# hmc241.net
KiCad netlist of a schematic drawn in EasyEDA Pro
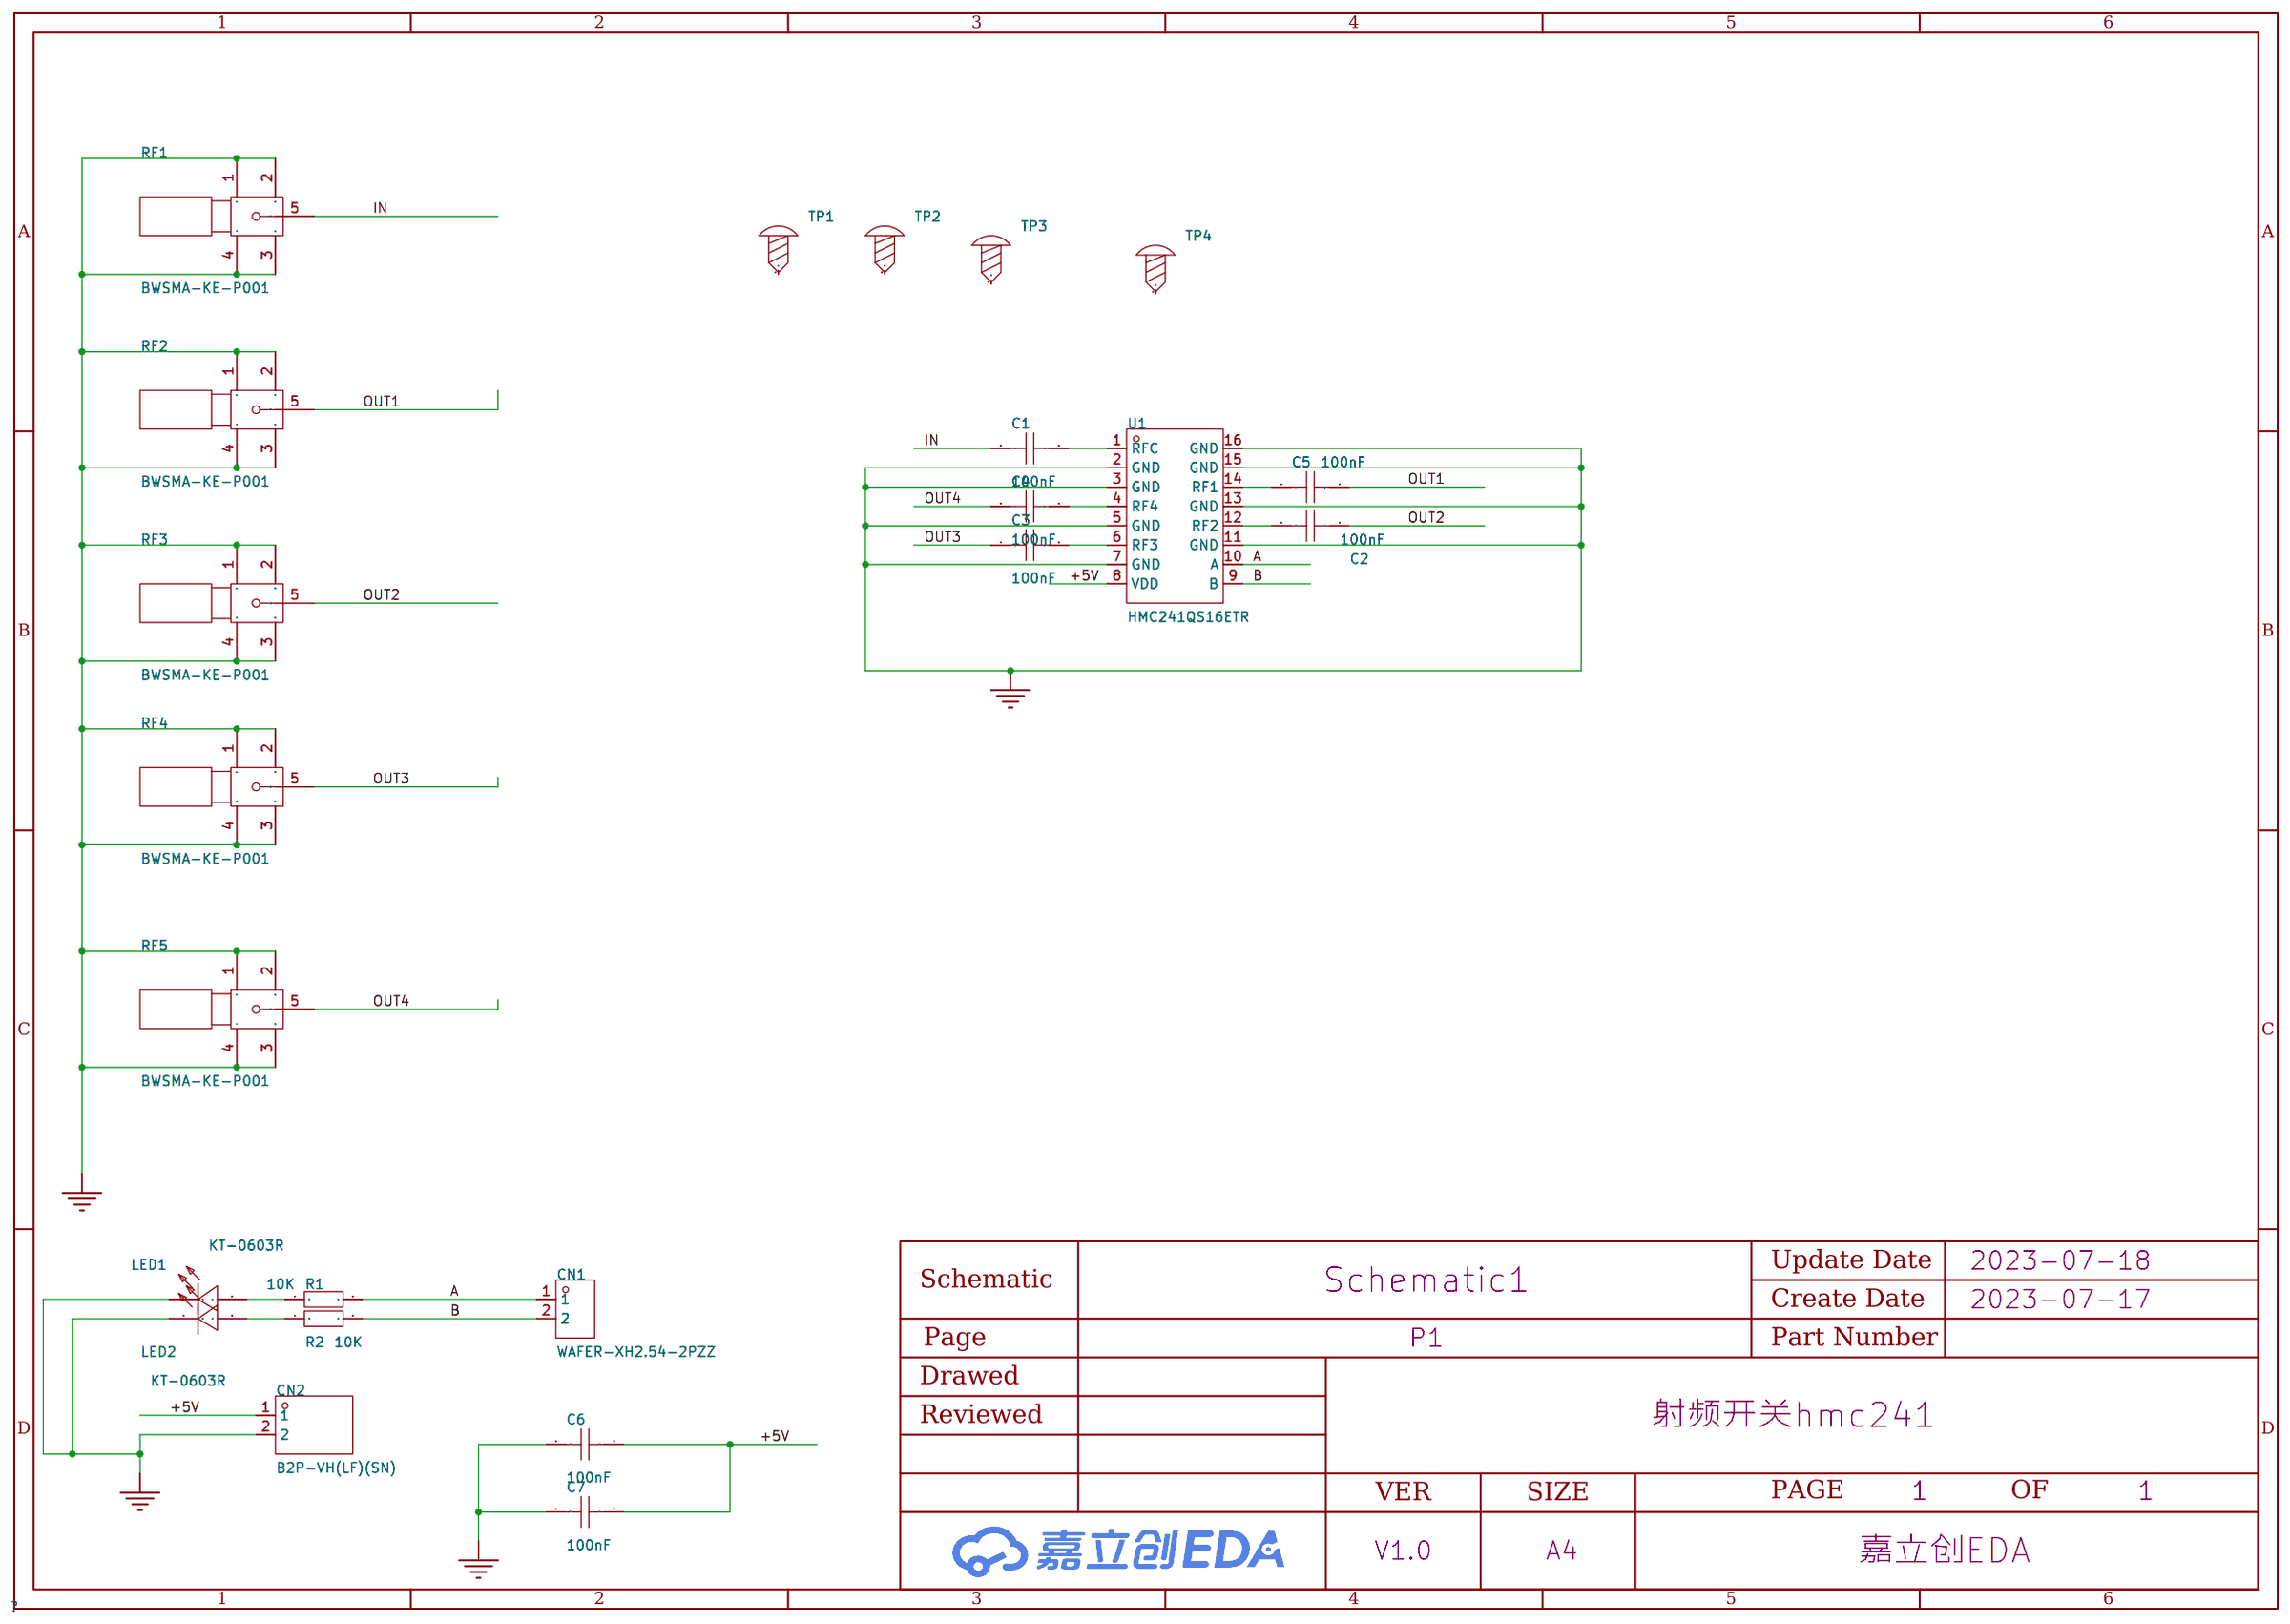
[diagram p0: schematic sheet]

(export (version "E")
  (design (tool "Eeschema 10.0.6"))
  (components
    (comp (ref "C1")
      (value "100nF")
      (footprint "easyedapro:C0603")
      (libsource (lib "easyedapro") (part "CapAcitance"))
    )
    (comp (ref "C2")
      (value "100nF")
      (footprint "easyedapro:C0603")
      (libsource (lib "easyedapro") (part "CapAcitance"))
    )
    (comp (ref "C3")
      (value "100nF")
      (footprint "easyedapro:C0603")
      (libsource (lib "easyedapro") (part "CapAcitance"))
    )
    (comp (ref "C4")
      (value "100nF")
      (footprint "easyedapro:C0603")
      (libsource (lib "easyedapro") (part "CapAcitance"))
    )
    (comp (ref "C5")
      (value "100nF")
      (footprint "easyedapro:C0603")
      (libsource (lib "easyedapro") (part "CapAcitance"))
    )
    (comp (ref "C6")
      (value "100nF")
      (footprint "easyedapro:C0603")
      (libsource (lib "easyedapro") (part "CapAcitance"))
    )
    (comp (ref "C7")
      (value "100nF")
      (footprint "easyedapro:C0603")
      (libsource (lib "easyedapro") (part "CapAcitance"))
    )
    (comp (ref "CN1")
      (value "WAFER-XH2.54-2PZZ")
      (footprint "easyedapro:CONN-TH_XH2.54-2P")
      (fields (field (name "Manufacturer") "XUNPU(讯普)"))
      (libsource (lib "easyedapro") (part "WAFER-XH2.54-2PZZ"))
    )
    (comp (ref "CN2")
      (value "B2P-VH(LF)(SN)")
      (footprint "easyedapro:CONN-TH_B2P-VH-LF-SN")
      (description "参考系列:VH;间距:3.96mm;插针结构:1x2P;排数:1;每排PIN数:2;行距:-;安装方式:-;触头材质:黄铜;")
      (fields (field (name "Manufacturer") "JST"))
      (libsource (lib "easyedapro") (part "B2P-VH (LF)(SN)"))
    )
    (comp (ref "LED1")
      (value "KT-0603R")
      (footprint "easyedapro:LED0603-RD")
      (description "发光颜色:红灯;二极管配置:-;透镜颜色:-;主波长:-;色温:-;功率:-;发光角度:-;安装方式:-;工作温度:-40°C~+85°C;")
      (fields (field (name "Manufacturer") "KENTO"))
      (libsource (lib "easyedapro") (part "KT-0603R"))
    )
    (comp (ref "LED2")
      (value "KT-0603R")
      (footprint "easyedapro:LED0603-RD")
      (description "发光颜色:红灯;二极管配置:-;透镜颜色:-;主波长:-;色温:-;功率:-;发光角度:-;安装方式:-;工作温度:-40°C~+85°C;")
      (fields (field (name "Manufacturer") "KENTO"))
      (libsource (lib "easyedapro") (part "KT-0603R"))
    )
    (comp (ref "R1") (value "10K") (footprint "easyedapro:R0603") (libsource (lib "easyedapro") (part "电阻")))
    (comp (ref "R2") (value "10K") (footprint "easyedapro:R0603") (libsource (lib "easyedapro") (part "电阻")))
    (comp (ref "RF1")
      (value "BWSMA-KE-P001")
      (footprint "easyedapro:SMA-SMD_BWSMA-KE-P001")
      (description "连接器类型:板端;射频系列:SMA;接口类型:内孔;端口数量:1;阻抗:50Ω;频率-最大值:12.4GHz;样式:偏脚;接口直径:5.2mm;接口长度/高度:-;工作温度范围:-;")
      (fields (field (name "Manufacturer") "BAT WIRELESS(蝙蝠无线)"))
      (libsource (lib "easyedapro") (part "BWSMA-KE-P001"))
    )
    (comp (ref "RF2")
      (value "BWSMA-KE-P001")
      (footprint "easyedapro:SMA-SMD_BWSMA-KE-P001")
      (description "连接器类型:板端;射频系列:SMA;接口类型:内孔;端口数量:1;阻抗:50Ω;频率-最大值:12.4GHz;样式:偏脚;接口直径:5.2mm;接口长度/高度:-;工作温度范围:-;")
      (fields (field (name "Manufacturer") "BAT WIRELESS(蝙蝠无线)"))
      (libsource (lib "easyedapro") (part "BWSMA-KE-P001"))
    )
    (comp (ref "RF3")
      (value "BWSMA-KE-P001")
      (footprint "easyedapro:SMA-SMD_BWSMA-KE-P001")
      (description "连接器类型:板端;射频系列:SMA;接口类型:内孔;端口数量:1;阻抗:50Ω;频率-最大值:12.4GHz;样式:偏脚;接口直径:5.2mm;接口长度/高度:-;工作温度范围:-;")
      (fields (field (name "Manufacturer") "BAT WIRELESS(蝙蝠无线)"))
      (libsource (lib "easyedapro") (part "BWSMA-KE-P001"))
    )
    (comp (ref "RF4")
      (value "BWSMA-KE-P001")
      (footprint "easyedapro:SMA-SMD_BWSMA-KE-P001")
      (description "连接器类型:板端;射频系列:SMA;接口类型:内孔;端口数量:1;阻抗:50Ω;频率-最大值:12.4GHz;样式:偏脚;接口直径:5.2mm;接口长度/高度:-;工作温度范围:-;")
      (fields (field (name "Manufacturer") "BAT WIRELESS(蝙蝠无线)"))
      (libsource (lib "easyedapro") (part "BWSMA-KE-P001"))
    )
    (comp (ref "RF5")
      (value "BWSMA-KE-P001")
      (footprint "easyedapro:SMA-SMD_BWSMA-KE-P001")
      (description "连接器类型:板端;射频系列:SMA;接口类型:内孔;端口数量:1;阻抗:50Ω;频率-最大值:12.4GHz;样式:偏脚;接口直径:5.2mm;接口长度/高度:-;工作温度范围:-;")
      (fields (field (name "Manufacturer") "BAT WIRELESS(蝙蝠无线)"))
      (libsource (lib "easyedapro") (part "BWSMA-KE-P001"))
    )
    (comp (ref "TP1") (value "~") (footprint "easyedapro:M3螺丝") (libsource (lib "easyedapro") (part "螺丝孔")))
    (comp (ref "TP2") (value "~") (footprint "easyedapro:M3螺丝") (libsource (lib "easyedapro") (part "螺丝孔")))
    (comp (ref "TP3") (value "~") (footprint "easyedapro:M3螺丝") (libsource (lib "easyedapro") (part "螺丝孔")))
    (comp (ref "TP4") (value "~") (footprint "easyedapro:M3螺丝") (libsource (lib "easyedapro") (part "螺丝孔")))
    (comp (ref "U1")
      (value "HMC241QS16ETR")
      (footprint "easyedapro:QSOP-16_L4.9-W3.9-P0.64-LS6.0-BL")
      (libsource (lib "easyedapro") (part "HMC241QS16ETR"))
    )
  )
  (nets
    (net (code "1") (name "/+5V") (class "Default")
      (node (ref "C6") (pin "2") (pinfunction "2_2") (pintype "input"))
      (node (ref "C7") (pin "2") (pinfunction "2_2") (pintype "input"))
      (node (ref "CN2") (pin "1") (pinfunction "1_1") (pintype "input"))
      (node (ref "U1") (pin "8") (pinfunction "VDD_8") (pintype "input"))
    )
    (net (code "2") (name "/A") (class "Default")
      (node (ref "CN1") (pin "1") (pinfunction "1_1") (pintype "input"))
      (node (ref "R1") (pin "2") (pinfunction "2_2") (pintype "input"))
      (node (ref "U1") (pin "10") (pinfunction "A_10") (pintype "input"))
    )
    (net (code "3") (name "/B") (class "Default")
      (node (ref "CN1") (pin "2") (pinfunction "2_2") (pintype "input"))
      (node (ref "R2") (pin "2") (pinfunction "2_2") (pintype "input"))
      (node (ref "U1") (pin "9") (pinfunction "B_9") (pintype "input"))
    )
    (net (code "4") (name "/IN") (class "Default")
      (node (ref "C1") (pin "1") (pinfunction "1_1") (pintype "input"))
      (node (ref "RF1") (pin "5") (pinfunction "5_5") (pintype "input"))
    )
    (net (code "5") (name "/OUT1") (class "Default")
      (node (ref "C5") (pin "2") (pinfunction "2_2") (pintype "input"))
      (node (ref "RF2") (pin "5") (pinfunction "5_5") (pintype "input"))
    )
    (net (code "6") (name "/OUT2") (class "Default")
      (node (ref "C2") (pin "2") (pinfunction "2_2") (pintype "input"))
      (node (ref "RF3") (pin "5") (pinfunction "5_5") (pintype "input"))
    )
    (net (code "7") (name "/OUT3") (class "Default")
      (node (ref "C3") (pin "1") (pinfunction "1_1") (pintype "input"))
      (node (ref "RF4") (pin "5") (pinfunction "5_5") (pintype "input"))
    )
    (net (code "8") (name "/OUT4") (class "Default")
      (node (ref "C4") (pin "1") (pinfunction "1_1") (pintype "input"))
      (node (ref "RF5") (pin "5") (pinfunction "5_5") (pintype "input"))
    )
    (net (code "9") (name "GND") (class "Default")
      (node (ref "C6") (pin "1") (pinfunction "1_1") (pintype "input"))
      (node (ref "C7") (pin "1") (pinfunction "1_1") (pintype "input"))
      (node (ref "CN2") (pin "2") (pinfunction "2_2") (pintype "input"))
      (node (ref "LED1") (pin "1") (pinfunction "K_1") (pintype "input"))
      (node (ref "LED2") (pin "1") (pinfunction "K_1") (pintype "input"))
      (node (ref "RF1") (pin "1") (pinfunction "1_1") (pintype "input"))
      (node (ref "RF1") (pin "2") (pinfunction "2_2") (pintype "input"))
      (node (ref "RF1") (pin "3") (pinfunction "3_3") (pintype "input"))
      (node (ref "RF1") (pin "4") (pinfunction "4_4") (pintype "input"))
      (node (ref "RF2") (pin "1") (pinfunction "1_1") (pintype "input"))
      (node (ref "RF2") (pin "2") (pinfunction "2_2") (pintype "input"))
      (node (ref "RF2") (pin "3") (pinfunction "3_3") (pintype "input"))
      (node (ref "RF2") (pin "4") (pinfunction "4_4") (pintype "input"))
      (node (ref "RF3") (pin "1") (pinfunction "1_1") (pintype "input"))
      (node (ref "RF3") (pin "2") (pinfunction "2_2") (pintype "input"))
      (node (ref "RF3") (pin "3") (pinfunction "3_3") (pintype "input"))
      (node (ref "RF3") (pin "4") (pinfunction "4_4") (pintype "input"))
      (node (ref "RF4") (pin "1") (pinfunction "1_1") (pintype "input"))
      (node (ref "RF4") (pin "2") (pinfunction "2_2") (pintype "input"))
      (node (ref "RF4") (pin "3") (pinfunction "3_3") (pintype "input"))
      (node (ref "RF4") (pin "4") (pinfunction "4_4") (pintype "input"))
      (node (ref "RF5") (pin "1") (pinfunction "1_1") (pintype "input"))
      (node (ref "RF5") (pin "2") (pinfunction "2_2") (pintype "input"))
      (node (ref "RF5") (pin "3") (pinfunction "3_3") (pintype "input"))
      (node (ref "RF5") (pin "4") (pinfunction "4_4") (pintype "input"))
      (node (ref "U1") (pin "11") (pinfunction "GND_11") (pintype "input"))
      (node (ref "U1") (pin "13") (pinfunction "GND_13") (pintype "input"))
      (node (ref "U1") (pin "15") (pinfunction "GND_15") (pintype "input"))
      (node (ref "U1") (pin "16") (pinfunction "GND_16") (pintype "input"))
      (node (ref "U1") (pin "2") (pinfunction "GND_2") (pintype "input"))
      (node (ref "U1") (pin "3") (pinfunction "GND_3") (pintype "input"))
      (node (ref "U1") (pin "5") (pinfunction "GND_5") (pintype "input"))
      (node (ref "U1") (pin "7") (pinfunction "GND_7") (pintype "input"))
    )
    (net (code "10") (name "Net-(LED1-A)") (class "Default")
      (node (ref "LED1") (pin "2") (pinfunction "A_2") (pintype "input"))
      (node (ref "R1") (pin "1") (pinfunction "1_1") (pintype "input"))
    )
    (net (code "11") (name "Net-(LED2-A)") (class "Default")
      (node (ref "LED2") (pin "2") (pinfunction "A_2") (pintype "input"))
      (node (ref "R2") (pin "1") (pinfunction "1_1") (pintype "input"))
    )
    (net (code "12") (name "Net-(U1-RF1)") (class "Default")
      (node (ref "C5") (pin "1") (pinfunction "1_1") (pintype "input"))
      (node (ref "U1") (pin "14") (pinfunction "RF1_14") (pintype "input"))
    )
    (net (code "13") (name "Net-(U1-RF2)") (class "Default")
      (node (ref "C2") (pin "1") (pinfunction "1_1") (pintype "input"))
      (node (ref "U1") (pin "12") (pinfunction "RF2_12") (pintype "input"))
    )
    (net (code "14") (name "Net-(U1-RF3)") (class "Default")
      (node (ref "C3") (pin "2") (pinfunction "2_2") (pintype "input"))
      (node (ref "U1") (pin "6") (pinfunction "RF3_6") (pintype "input"))
    )
    (net (code "15") (name "Net-(U1-RF4)") (class "Default")
      (node (ref "C4") (pin "2") (pinfunction "2_2") (pintype "input"))
      (node (ref "U1") (pin "4") (pinfunction "RF4_4") (pintype "input"))
    )
    (net (code "16") (name "Net-(U1-RFC)") (class "Default")
      (node (ref "C1") (pin "2") (pinfunction "2_2") (pintype "input"))
      (node (ref "U1") (pin "1") (pinfunction "RFC_1") (pintype "input"))
    )
    (net (code "17") (name "unconnected-(TP1-Pad1)") (class "Default")
      (node (ref "TP1") (pin "1") (pinfunction "1_1") (pintype "input"))
    )
    (net (code "18") (name "unconnected-(TP2-Pad1)") (class "Default")
      (node (ref "TP2") (pin "1") (pinfunction "1_1") (pintype "input"))
    )
    (net (code "19") (name "unconnected-(TP3-Pad1)") (class "Default")
      (node (ref "TP3") (pin "1") (pinfunction "1_1") (pintype "input"))
    )
    (net (code "20") (name "unconnected-(TP4-Pad1)") (class "Default")
      (node (ref "TP4") (pin "1") (pinfunction "1_1") (pintype "input"))
    )
  )
)
